# POWER.net
KiCad netlist of a schematic drawn in Altium Designer
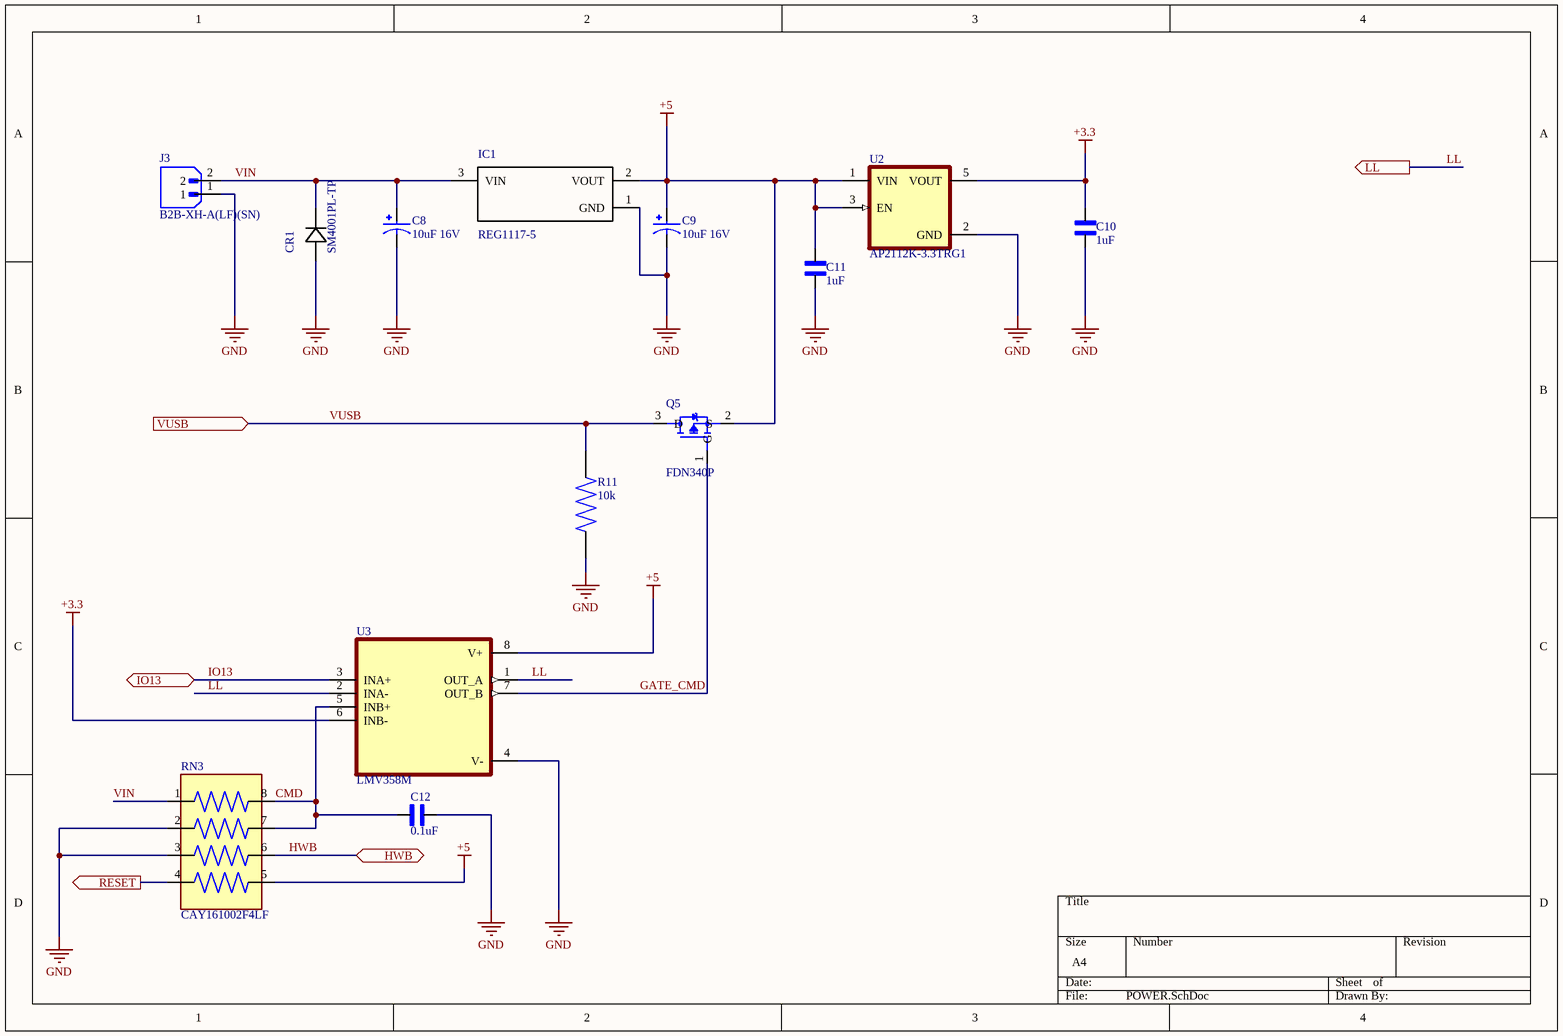
[diagram p0: POWER.SchDoc]

(export (version "E")
  (design (tool "Eeschema 10.0.6"))
  (components
    (comp (ref "C8")
      (value "10uF 16V")
      (footprint "CAP_EEEHB1C100AR")
      (description "10ÂµF 16V Aluminum Electrolytic Capacitors Radial, Can - SMD 2000 Hrs @ 105Â°C")
      (fields (field (name "MP") "EEE-HB1C100AR") (field (name "MF") "Panasonic"))
      (libsource (lib "RFID") (part "EEEHB1C100AR"))
    )
    (comp (ref "C9")
      (value "10uF 16V")
      (footprint "CAP_EEEHB1C100AR")
      (description "10ÂµF 16V Aluminum Electrolytic Capacitors Radial, Can - SMD 2000 Hrs @ 105Â°C")
      (fields (field (name "MP") "EEE-HB1C100AR") (field (name "MF") "Panasonic"))
      (libsource (lib "RFID") (part "EEEHB1C100AR"))
    )
    (comp (ref "C10")
      (value "1uF")
      (footprint "CAPC1608X90N")
      (fields (field (name "MP") "C0603C105K4RAC7411"))
      (libsource (lib "RFID") (part "C0603C105K4RAC7411"))
    )
    (comp (ref "C11")
      (value "1uF")
      (footprint "CAPC1608X90N")
      (fields (field (name "MP") "C0603C105K4RAC7411"))
      (libsource (lib "") (part "C0603C105K4RAC7411_1"))
    )
    (comp (ref "C12")
      (value "0.1uF")
      (footprint "CAPC1608X90")
      (description "Capacitor;Ceramic;Cap;.0.1uF;Tol+5%;SMT;Vol-Rtg 16V;X7R;TR ¦ KEMET C0603C104J4RACTU")
      (fields (field (name "MF") "KEMET") (field (name "MP") "C0603C104J4RACTU"))
      (libsource (lib "RFID") (part "C0603C104J4RACTU"))
    )
    (comp (ref "CR1")
      (value "SM4001PL-TP")
      (footprint "*SOD-123FL_MCC")
      (description "Diode Standard 50 V 1A Surface Mount SOD-123FL")
      (fields (field (name "MF") "Micro Commercial"))
      (libsource (lib "RFID") (part "SM4001PL-TP"))
    )
    (comp (ref "IC1")
      (value "REG1117-5")
      (footprint "*SOT230P700X180-4N")
      (description "800-mA, 15-V, linear voltage regulator")
      (fields (field (name "MF") "Texas Instruments"))
      (libsource (lib "RFID") (part "REG1117-5"))
    )
    (comp (ref "J3")
      (value "B2B-XH-A(LF)(SN)")
      (footprint "JST_B2B-XH-A(LF)(SN)")
      (description "Connector Header Through Hole 2 position 0.098 (2.50mm)")
      (fields (field (name "MF") "JST Sales"))
      (libsource (lib "RFID") (part "B2B-XH-A(LF)(SN)"))
    )
    (comp (ref "Q5")
      (value "FDN340P")
      (footprint "SOT95P240X120-3N")
      (description "P-Channel 20 V 2A (Ta) 500mW (Ta) Surface Mount SOT-23-3")
      (fields (field (name "MF") "onsemi"))
      (libsource (lib "RFID") (part "FDN340P"))
    )
    (comp (ref "R11")
      (value "10k")
      (footprint "RESC3115X65N")
      (description "Res Thick Film 1206 4.7K Ohm 1% 0.25W(1/4W) Â±100ppm/C Pad SMD T/R")
      (fields (field (name "MF") "TE Connectivity") (field (name "MP") "CRG1206F4K7/10"))
      (libsource (lib "RFID") (part "CRG1206F4K7/10"))
    )
    (comp (ref "RN3")
      (value "CAY161002F4LF")
      (footprint "RESCAF80P320X160X60-8N")
      (fields (field (name "MF") "Bourns Electronics"))
      (libsource (lib "RFID") (part "CAY161002F4LF"))
    )
    (comp (ref "U2")
      (value "AP2112K-3.3TRG1")
      (footprint "SOT95P285X140-5N")
      (description "Linear Voltage Regulator IC Positive Fixed 1 Output 600mA SOT-25")
      (fields (field (name "MF") "Diodes Inc."))
      (libsource (lib "RFID") (part "AP2112K-3.3TRG1"))
    )
    (comp (ref "U3")
      (value "LMV358M")
      (footprint "SOIC127P599X175-8N")
      (description "Dual, 5.5-V, 1-MHz op amp")
      (fields (field (name "MF") "Texas Instruments") (field (name "MP") "LMV358M/NOPB"))
      (libsource (lib "RFID") (part "LMV358M"))
    )
  )
  (nets
    (net (code "1") (name "+3.3") (class "Default")
      (node (ref "C10") (pin "2") (pinfunction "2_2") (pintype "passive"))
      (node (ref "U2") (pin "5") (pinfunction "VOUT_5") (pintype "power_in"))
      (node (ref "U3") (pin "6") (pinfunction "INB-_6") (pintype "passive"))
    )
    (net (code "2") (name "+5") (class "Default")
      (node (ref "C11") (pin "1") (pinfunction "1_1") (pintype "passive"))
      (node (ref "C9") (pin "1") (pinfunction "1_1") (pintype "passive"))
      (node (ref "IC1") (pin "2") (pinfunction "VOUT_2") (pintype "power_in"))
      (node (ref "Q5") (pin "2") (pinfunction "S_2") (pintype "passive"))
      (node (ref "RN3") (pin "5") (pinfunction "5_5") (pintype "passive"))
      (node (ref "U2") (pin "1") (pinfunction "VIN_1") (pintype "power_in"))
      (node (ref "U2") (pin "3") (pinfunction "EN_3") (pintype "input"))
      (node (ref "U3") (pin "8") (pinfunction "V+_8") (pintype "power_in"))
    )
    (net (code "3") (name "/CMD") (class "Default")
      (node (ref "C12") (pin "2") (pinfunction "2_2") (pintype "passive"))
      (node (ref "RN3") (pin "7") (pinfunction "7_7") (pintype "passive"))
      (node (ref "RN3") (pin "8") (pinfunction "8_8") (pintype "passive"))
      (node (ref "U3") (pin "5") (pinfunction "INB+_5") (pintype "passive"))
    )
    (net (code "4") (name "/GATE_CMD") (class "Default")
      (node (ref "Q5") (pin "1") (pinfunction "G_1") (pintype "passive"))
      (node (ref "U3") (pin "7") (pinfunction "OUT_B_7") (pintype "output"))
    )
    (net (code "5") (name "/HWB") (class "Default")
      (node (ref "RN3") (pin "6") (pinfunction "6_6") (pintype "passive"))
    )
    (net (code "6") (name "/IO13") (class "Default")
      (node (ref "U3") (pin "3") (pinfunction "INA+_3") (pintype "passive"))
    )
    (net (code "7") (name "/LL") (class "Default")
      (node (ref "U3") (pin "1") (pinfunction "OUT_A_1") (pintype "output"))
      (node (ref "U3") (pin "2") (pinfunction "INA-_2") (pintype "passive"))
    )
    (net (code "8") (name "/RESET") (class "Default")
      (node (ref "RN3") (pin "4") (pinfunction "4_4") (pintype "passive"))
    )
    (net (code "9") (name "/VIN") (class "Default")
      (node (ref "C8") (pin "1") (pinfunction "1_1") (pintype "passive"))
      (node (ref "CR1") (pin "1") (pinfunction "1_1") (pintype "passive"))
      (node (ref "IC1") (pin "3") (pinfunction "VIN_3") (pintype "passive"))
      (node (ref "J3") (pin "2") (pinfunction "2_2") (pintype "passive"))
      (node (ref "RN3") (pin "1") (pinfunction "1_1") (pintype "passive"))
    )
    (net (code "10") (name "/VUSB") (class "Default")
      (node (ref "Q5") (pin "3") (pinfunction "D_3") (pintype "passive"))
      (node (ref "R11") (pin "2") (pinfunction "2_2") (pintype "passive"))
    )
    (net (code "11") (name "GND") (class "Default")
      (node (ref "C10") (pin "1") (pinfunction "1_1") (pintype "passive"))
      (node (ref "C11") (pin "2") (pinfunction "2_2") (pintype "passive"))
      (node (ref "C12") (pin "1") (pinfunction "1_1") (pintype "passive"))
      (node (ref "C8") (pin "2") (pinfunction "2_2") (pintype "passive"))
      (node (ref "C9") (pin "2") (pinfunction "2_2") (pintype "passive"))
      (node (ref "CR1") (pin "2") (pinfunction "2_2") (pintype "passive"))
      (node (ref "IC1") (pin "1") (pinfunction "GND_1") (pintype "power_in"))
      (node (ref "J3") (pin "1") (pinfunction "1_1") (pintype "passive"))
      (node (ref "R11") (pin "1") (pinfunction "1_1") (pintype "passive"))
      (node (ref "RN3") (pin "2") (pinfunction "2_2") (pintype "passive"))
      (node (ref "RN3") (pin "3") (pinfunction "3_3") (pintype "passive"))
      (node (ref "U2") (pin "2") (pinfunction "GND_2") (pintype "power_in"))
      (node (ref "U3") (pin "4") (pinfunction "V-_4") (pintype "power_in"))
    )
  )
)
